# design.net
KiCad netlist of a schematic drawn in Altium Designer
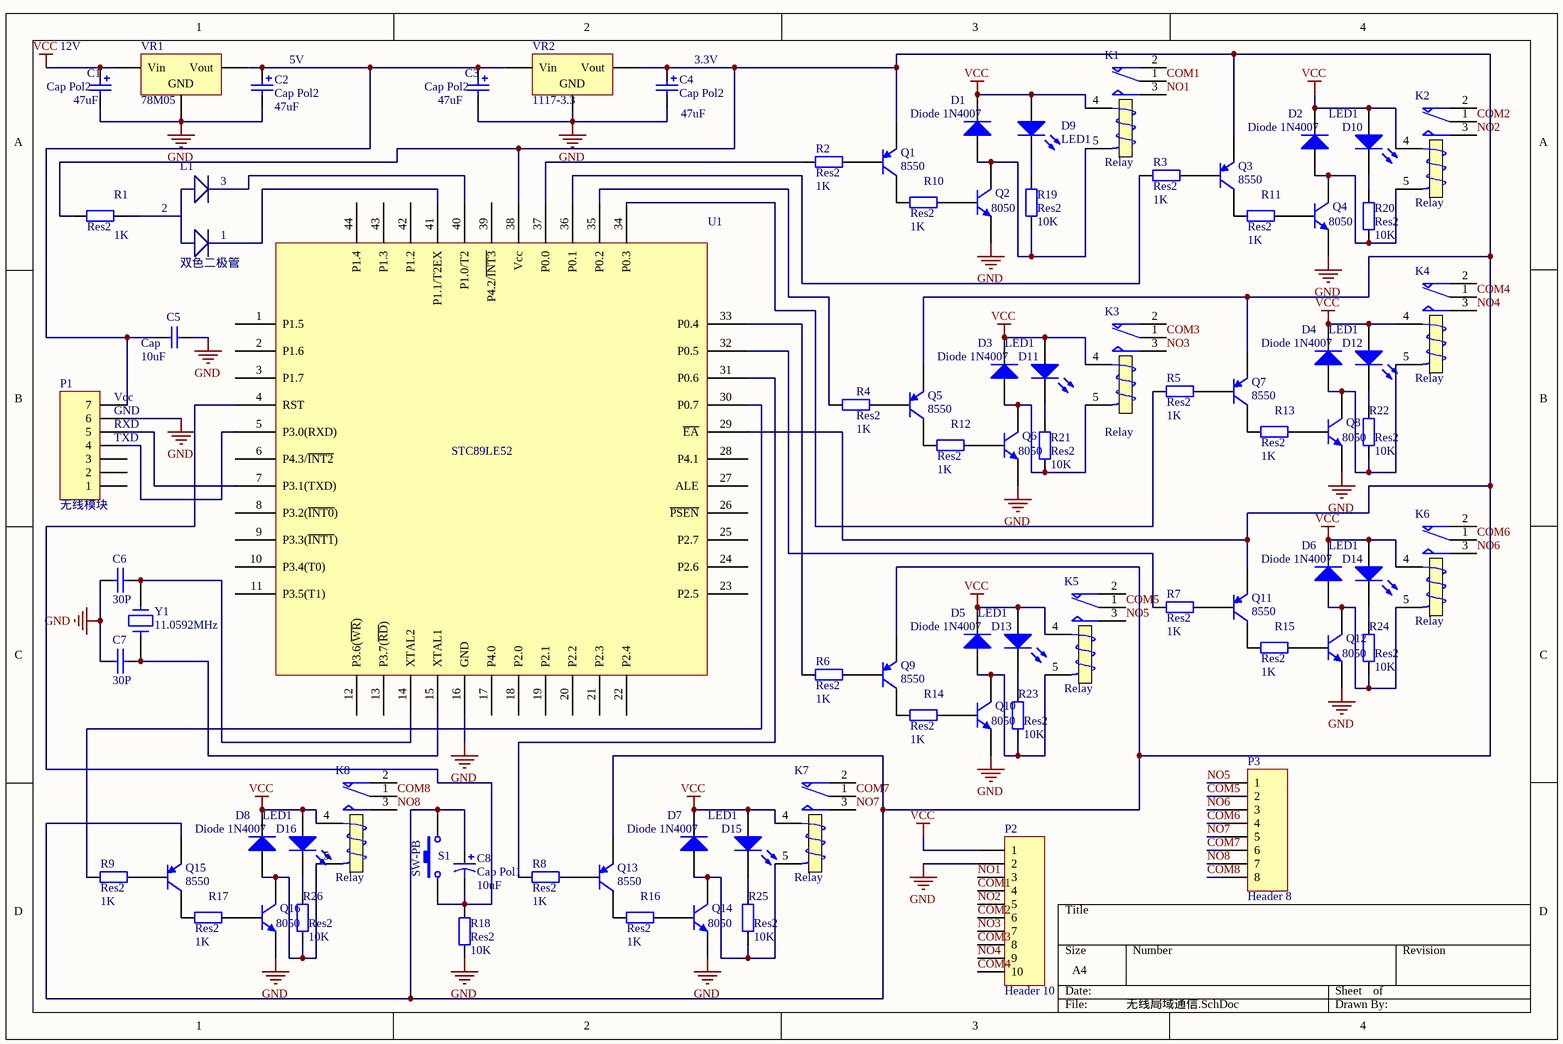
[diagram p0: 无线局域通信.SchDoc]

(export (version "E")
  (design (tool "Eeschema 10.0.6"))
  (components
    (comp (ref "C1")
      (value "Cap Pol2")
      (footprint "CAP_D6_3MM")
      (description "Polarized Capacitor (Axial)")
      (fields (field (name "ALTIUM_VALUE") "47uF") (field (name "PUBLISHER") "Altium Limited"))
      (libsource (lib "Miscellaneous Devices") (part "Cap Pol2"))
    )
    (comp (ref "C2")
      (value "Cap Pol2")
      (footprint "CAP_D6_3MM")
      (description "Polarized Capacitor (Axial)")
      (fields (field (name "ALTIUM_VALUE") "47uF") (field (name "PUBLISHER") "Altium Limited"))
      (libsource (lib "Miscellaneous Devices") (part "Cap Pol2"))
    )
    (comp (ref "C3")
      (value "Cap Pol2")
      (footprint "CAP_D6_3MM")
      (description "Polarized Capacitor (Axial)")
      (fields (field (name "ALTIUM_VALUE") "47uF") (field (name "PUBLISHER") "Altium Limited"))
      (libsource (lib "Miscellaneous Devices") (part "Cap Pol2"))
    )
    (comp (ref "C4")
      (value "Cap Pol2")
      (footprint "CAP_D6_3MM")
      (description "Polarized Capacitor (Axial)")
      (fields (field (name "ALTIUM_VALUE") "47uF") (field (name "PUBLISHER") "Altium Limited"))
      (libsource (lib "Miscellaneous Devices") (part "Cap Pol2"))
    )
    (comp (ref "C5")
      (value "Cap")
      (footprint "RAD0.1")
      (description "Capacitor")
      (fields (field (name "ALTIUM_VALUE") "10uF") (field (name "PUBLISHER") "Altium Limited"))
      (libsource (lib "Miscellaneous Devices") (part "Cap"))
    )
    (comp (ref "C6")
      (value "30P")
      (footprint "0603")
      (description "Capacitor")
      (libsource (lib "*") (part "MY_C_CAP"))
    )
    (comp (ref "C7")
      (value "30P")
      (footprint "0603")
      (description "Capacitor")
      (libsource (lib "*") (part "MY_C_CAP"))
    )
    (comp (ref "C8")
      (value "Cap Pol1")
      (footprint "CAP_D6_3MM")
      (description "Polarized Capacitor (Radial)")
      (fields (field (name "ALTIUM_VALUE") "10uF") (field (name "PUBLISHER") "Altium Limited"))
      (libsource (lib "Miscellaneous Devices") (part "Cap Pol1"))
    )
    (comp (ref "D1")
      (value "Diode 1N4007")
      (footprint "DO-41")
      (description "1 Amp General Purpose Rectifier")
      (fields (field (name "PUBLISHER") "Altium Limited"))
      (libsource (lib "Miscellaneous Devices") (part "Diode 1N4007"))
    )
    (comp (ref "D2")
      (value "Diode 1N4007")
      (footprint "DO-41")
      (description "1 Amp General Purpose Rectifier")
      (fields (field (name "PUBLISHER") "Altium Limited"))
      (libsource (lib "Miscellaneous Devices") (part "Diode 1N4007"))
    )
    (comp (ref "D3")
      (value "Diode 1N4007")
      (footprint "DO-41")
      (description "1 Amp General Purpose Rectifier")
      (fields (field (name "PUBLISHER") "Altium Limited"))
      (libsource (lib "Miscellaneous Devices") (part "Diode 1N4007"))
    )
    (comp (ref "D4")
      (value "Diode 1N4007")
      (footprint "DO-41")
      (description "1 Amp General Purpose Rectifier")
      (fields (field (name "PUBLISHER") "Altium Limited"))
      (libsource (lib "Miscellaneous Devices") (part "Diode 1N4007"))
    )
    (comp (ref "D5")
      (value "Diode 1N4007")
      (footprint "DO-41")
      (description "1 Amp General Purpose Rectifier")
      (fields (field (name "PUBLISHER") "Altium Limited"))
      (libsource (lib "Miscellaneous Devices") (part "Diode 1N4007"))
    )
    (comp (ref "D6")
      (value "Diode 1N4007")
      (footprint "DO-41")
      (description "1 Amp General Purpose Rectifier")
      (fields (field (name "PUBLISHER") "Altium Limited"))
      (libsource (lib "Miscellaneous Devices") (part "Diode 1N4007"))
    )
    (comp (ref "D7")
      (value "Diode 1N4007")
      (footprint "DO-41")
      (description "1 Amp General Purpose Rectifier")
      (fields (field (name "PUBLISHER") "Altium Limited"))
      (libsource (lib "Miscellaneous Devices") (part "Diode 1N4007"))
    )
    (comp (ref "D8")
      (value "Diode 1N4007")
      (footprint "DO-41")
      (description "1 Amp General Purpose Rectifier")
      (fields (field (name "PUBLISHER") "Altium Limited"))
      (libsource (lib "Miscellaneous Devices") (part "Diode 1N4007"))
    )
    (comp (ref "D9")
      (value "LED1")
      (footprint "LED-1")
      (description "Typical RED GaAs LED")
      (fields (field (name "PUBLISHER") "Altium Limited"))
      (libsource (lib "Miscellaneous Devices") (part "LED1"))
    )
    (comp (ref "D10")
      (value "LED1")
      (footprint "LED-1")
      (description "Typical RED GaAs LED")
      (fields (field (name "PUBLISHER") "Altium Limited"))
      (libsource (lib "Miscellaneous Devices") (part "LED1"))
    )
    (comp (ref "D11")
      (value "LED1")
      (footprint "LED-1")
      (description "Typical RED GaAs LED")
      (fields (field (name "PUBLISHER") "Altium Limited"))
      (libsource (lib "Miscellaneous Devices") (part "LED1"))
    )
    (comp (ref "D12")
      (value "LED1")
      (footprint "LED-1")
      (description "Typical RED GaAs LED")
      (fields (field (name "PUBLISHER") "Altium Limited"))
      (libsource (lib "Miscellaneous Devices") (part "LED1"))
    )
    (comp (ref "D13")
      (value "LED1")
      (footprint "LED-1")
      (description "Typical RED GaAs LED")
      (fields (field (name "PUBLISHER") "Altium Limited"))
      (libsource (lib "Miscellaneous Devices") (part "LED1"))
    )
    (comp (ref "D14")
      (value "LED1")
      (footprint "LED-1")
      (description "Typical RED GaAs LED")
      (fields (field (name "PUBLISHER") "Altium Limited"))
      (libsource (lib "Miscellaneous Devices") (part "LED1"))
    )
    (comp (ref "D15")
      (value "LED1")
      (footprint "LED-1")
      (description "Typical RED GaAs LED")
      (fields (field (name "PUBLISHER") "Altium Limited"))
      (libsource (lib "Miscellaneous Devices") (part "LED1"))
    )
    (comp (ref "D16")
      (value "LED1")
      (footprint "LED-1")
      (description "Typical RED GaAs LED")
      (fields (field (name "PUBLISHER") "Altium Limited"))
      (libsource (lib "Miscellaneous Devices") (part "LED1"))
    )
    (comp (ref "K1")
      (value "Relay")
      (footprint "继电器")
      (description "SPDT Relay")
      (fields (field (name "PUBLISHER") "Altium Limited"))
      (libsource (lib "Miscellaneous Devices") (part "Relay"))
    )
    (comp (ref "K2")
      (value "Relay")
      (footprint "继电器")
      (description "SPDT Relay")
      (fields (field (name "PUBLISHER") "Altium Limited"))
      (libsource (lib "Miscellaneous Devices") (part "Relay"))
    )
    (comp (ref "K3")
      (value "Relay")
      (footprint "继电器")
      (description "SPDT Relay")
      (fields (field (name "PUBLISHER") "Altium Limited"))
      (libsource (lib "Miscellaneous Devices") (part "Relay"))
    )
    (comp (ref "K4")
      (value "Relay")
      (footprint "继电器")
      (description "SPDT Relay")
      (fields (field (name "PUBLISHER") "Altium Limited"))
      (libsource (lib "Miscellaneous Devices") (part "Relay"))
    )
    (comp (ref "K5")
      (value "Relay")
      (footprint "继电器")
      (description "SPDT Relay")
      (fields (field (name "PUBLISHER") "Altium Limited"))
      (libsource (lib "Miscellaneous Devices") (part "Relay"))
    )
    (comp (ref "K6")
      (value "Relay")
      (footprint "继电器")
      (description "SPDT Relay")
      (fields (field (name "PUBLISHER") "Altium Limited"))
      (libsource (lib "Miscellaneous Devices") (part "Relay"))
    )
    (comp (ref "K7")
      (value "Relay")
      (footprint "继电器")
      (description "SPDT Relay")
      (fields (field (name "PUBLISHER") "Altium Limited"))
      (libsource (lib "Miscellaneous Devices") (part "Relay"))
    )
    (comp (ref "K8")
      (value "Relay")
      (footprint "继电器")
      (description "SPDT Relay")
      (fields (field (name "PUBLISHER") "Altium Limited"))
      (libsource (lib "Miscellaneous Devices") (part "Relay"))
    )
    (comp (ref "L1") (value "双色二极管") (footprint "TO-205AF") (libsource (lib "PCB_Project1") (part "双色二极管")))
    (comp (ref "P1")
      (value "无线模块")
      (footprint "P1")
      (description "Header, 7-Pin")
      (fields (field (name "PUBLISHER") "Altium Limited"))
      (libsource (lib "Miscellaneous Connectors") (part "MHDR1X7"))
    )
    (comp (ref "P2")
      (value "Header 10")
      (footprint "P2")
      (description "Header, 10-Pin")
      (fields (field (name "PUBLISHER") "Altium Limited"))
      (libsource (lib "Miscellaneous Connectors") (part "Header 10"))
    )
    (comp (ref "P3")
      (value "Header 8")
      (footprint "P3")
      (description "Header, 8-Pin")
      (fields (field (name "PUBLISHER") "Altium Limited"))
      (libsource (lib "Miscellaneous Connectors") (part "Header 8"))
    )
    (comp (ref "Q1")
      (value "8550")
      (footprint "SOT-23B_N")
      (description "PNP Bipolar Transistor")
      (fields (field (name "PUBLISHER") "Altium Limited"))
      (libsource (lib "Miscellaneous Devices") (part "PNP"))
    )
    (comp (ref "Q2")
      (value "8050")
      (footprint "SOT-23B_N")
      (description "NPN Bipolar Transistor")
      (fields (field (name "PUBLISHER") "Altium Limited"))
      (libsource (lib "Miscellaneous Devices") (part "QNPN"))
    )
    (comp (ref "Q3")
      (value "8550")
      (footprint "SOT-23B_N")
      (description "PNP Bipolar Transistor")
      (fields (field (name "PUBLISHER") "Altium Limited"))
      (libsource (lib "Miscellaneous Devices") (part "PNP"))
    )
    (comp (ref "Q4")
      (value "8050")
      (footprint "SOT-23B_N")
      (description "NPN Bipolar Transistor")
      (fields (field (name "PUBLISHER") "Altium Limited"))
      (libsource (lib "Miscellaneous Devices") (part "QNPN"))
    )
    (comp (ref "Q5")
      (value "8550")
      (footprint "SOT-23B_N")
      (description "PNP Bipolar Transistor")
      (fields (field (name "PUBLISHER") "Altium Limited"))
      (libsource (lib "Miscellaneous Devices") (part "PNP"))
    )
    (comp (ref "Q6")
      (value "8050")
      (footprint "SOT-23B_N")
      (description "NPN Bipolar Transistor")
      (fields (field (name "PUBLISHER") "Altium Limited"))
      (libsource (lib "Miscellaneous Devices") (part "QNPN"))
    )
    (comp (ref "Q7")
      (value "8550")
      (footprint "SOT-23B_N")
      (description "PNP Bipolar Transistor")
      (fields (field (name "PUBLISHER") "Altium Limited"))
      (libsource (lib "Miscellaneous Devices") (part "PNP"))
    )
    (comp (ref "Q8")
      (value "8050")
      (footprint "SOT-23B_N")
      (description "NPN Bipolar Transistor")
      (fields (field (name "PUBLISHER") "Altium Limited"))
      (libsource (lib "Miscellaneous Devices") (part "QNPN"))
    )
    (comp (ref "Q9")
      (value "8550")
      (footprint "SOT-23B_N")
      (description "PNP Bipolar Transistor")
      (fields (field (name "PUBLISHER") "Altium Limited"))
      (libsource (lib "Miscellaneous Devices") (part "PNP"))
    )
    (comp (ref "Q10")
      (value "8050")
      (footprint "SOT-23B_N")
      (description "NPN Bipolar Transistor")
      (fields (field (name "PUBLISHER") "Altium Limited"))
      (libsource (lib "Miscellaneous Devices") (part "QNPN"))
    )
    (comp (ref "Q11")
      (value "8550")
      (footprint "SOT-23B_N")
      (description "PNP Bipolar Transistor")
      (fields (field (name "PUBLISHER") "Altium Limited"))
      (libsource (lib "Miscellaneous Devices") (part "PNP"))
    )
    (comp (ref "Q12")
      (value "8050")
      (footprint "SOT-23B_N")
      (description "NPN Bipolar Transistor")
      (fields (field (name "PUBLISHER") "Altium Limited"))
      (libsource (lib "Miscellaneous Devices") (part "QNPN"))
    )
    (comp (ref "Q13")
      (value "8550")
      (footprint "SOT-23B_N")
      (description "PNP Bipolar Transistor")
      (fields (field (name "PUBLISHER") "Altium Limited"))
      (libsource (lib "Miscellaneous Devices") (part "PNP"))
    )
    (comp (ref "Q14")
      (value "8050")
      (footprint "SOT-23B_N")
      (description "NPN Bipolar Transistor")
      (fields (field (name "PUBLISHER") "Altium Limited"))
      (libsource (lib "Miscellaneous Devices") (part "QNPN"))
    )
    (comp (ref "Q15")
      (value "8550")
      (footprint "SOT-23B_N")
      (description "PNP Bipolar Transistor")
      (fields (field (name "PUBLISHER") "Altium Limited"))
      (libsource (lib "Miscellaneous Devices") (part "PNP"))
    )
    (comp (ref "Q16")
      (value "8050")
      (footprint "SOT-23B_N")
      (description "NPN Bipolar Transistor")
      (fields (field (name "PUBLISHER") "Altium Limited"))
      (libsource (lib "Miscellaneous Devices") (part "QNPN"))
    )
    (comp (ref "R1")
      (value "Res2")
      (footprint "0603")
      (description "Resistor")
      (fields (field (name "ALTIUM_VALUE") "1K") (field (name "PUBLISHER") "Altium Limited"))
      (libsource (lib "") (part "Res2_1"))
    )
    (comp (ref "R2")
      (value "Res2")
      (footprint "0603")
      (description "Resistor")
      (fields (field (name "ALTIUM_VALUE") "1K") (field (name "PUBLISHER") "Altium Limited"))
      (libsource (lib "") (part "Res2_1"))
    )
    (comp (ref "R3")
      (value "Res2")
      (footprint "0603")
      (description "Resistor")
      (fields (field (name "ALTIUM_VALUE") "1K") (field (name "PUBLISHER") "Altium Limited"))
      (libsource (lib "") (part "Res2_1"))
    )
    (comp (ref "R4")
      (value "Res2")
      (footprint "0603")
      (description "Resistor")
      (fields (field (name "ALTIUM_VALUE") "1K") (field (name "PUBLISHER") "Altium Limited"))
      (libsource (lib "") (part "Res2_1"))
    )
    (comp (ref "R5")
      (value "Res2")
      (footprint "0603")
      (description "Resistor")
      (fields (field (name "ALTIUM_VALUE") "1K") (field (name "PUBLISHER") "Altium Limited"))
      (libsource (lib "") (part "Res2_1"))
    )
    (comp (ref "R6")
      (value "Res2")
      (footprint "0603")
      (description "Resistor")
      (fields (field (name "ALTIUM_VALUE") "1K") (field (name "PUBLISHER") "Altium Limited"))
      (libsource (lib "") (part "Res2_1"))
    )
    (comp (ref "R7")
      (value "Res2")
      (footprint "0603")
      (description "Resistor")
      (fields (field (name "ALTIUM_VALUE") "1K") (field (name "PUBLISHER") "Altium Limited"))
      (libsource (lib "") (part "Res2_1"))
    )
    (comp (ref "R8")
      (value "Res2")
      (footprint "0603")
      (description "Resistor")
      (fields (field (name "ALTIUM_VALUE") "1K") (field (name "PUBLISHER") "Altium Limited"))
      (libsource (lib "") (part "Res2_1"))
    )
    (comp (ref "R9")
      (value "Res2")
      (footprint "0603")
      (description "Resistor")
      (fields (field (name "ALTIUM_VALUE") "1K") (field (name "PUBLISHER") "Altium Limited"))
      (libsource (lib "") (part "Res2_1"))
    )
    (comp (ref "R10")
      (value "Res2")
      (footprint "0603")
      (description "Resistor")
      (fields (field (name "ALTIUM_VALUE") "1K") (field (name "PUBLISHER") "Altium Limited"))
      (libsource (lib "") (part "Res2_1"))
    )
    (comp (ref "R11")
      (value "Res2")
      (footprint "0603")
      (description "Resistor")
      (fields (field (name "ALTIUM_VALUE") "1K") (field (name "PUBLISHER") "Altium Limited"))
      (libsource (lib "") (part "Res2_1"))
    )
    (comp (ref "R12")
      (value "Res2")
      (footprint "0603")
      (description "Resistor")
      (fields (field (name "ALTIUM_VALUE") "1K") (field (name "PUBLISHER") "Altium Limited"))
      (libsource (lib "") (part "Res2_1"))
    )
    (comp (ref "R13")
      (value "Res2")
      (footprint "0603")
      (description "Resistor")
      (fields (field (name "ALTIUM_VALUE") "1K") (field (name "PUBLISHER") "Altium Limited"))
      (libsource (lib "") (part "Res2_1"))
    )
    (comp (ref "R14")
      (value "Res2")
      (footprint "0603")
      (description "Resistor")
      (fields (field (name "ALTIUM_VALUE") "1K") (field (name "PUBLISHER") "Altium Limited"))
      (libsource (lib "") (part "Res2_1"))
    )
    (comp (ref "R15")
      (value "Res2")
      (footprint "0603")
      (description "Resistor")
      (fields (field (name "ALTIUM_VALUE") "1K") (field (name "PUBLISHER") "Altium Limited"))
      (libsource (lib "") (part "Res2_1"))
    )
    (comp (ref "R16")
      (value "Res2")
      (footprint "0603")
      (description "Resistor")
      (fields (field (name "ALTIUM_VALUE") "1K") (field (name "PUBLISHER") "Altium Limited"))
      (libsource (lib "") (part "Res2_1"))
    )
    (comp (ref "R17")
      (value "Res2")
      (footprint "0603")
      (description "Resistor")
      (fields (field (name "ALTIUM_VALUE") "1K") (field (name "PUBLISHER") "Altium Limited"))
      (libsource (lib "") (part "Res2_1"))
    )
    (comp (ref "R18")
      (value "Res2")
      (footprint "0603")
      (description "Resistor")
      (fields (field (name "ALTIUM_VALUE") "10K") (field (name "PUBLISHER") "Altium Limited"))
      (libsource (lib "Miscellaneous Devices") (part "Res2"))
    )
    (comp (ref "R19")
      (value "Res2")
      (footprint "0603")
      (description "Resistor")
      (fields (field (name "ALTIUM_VALUE") "10K") (field (name "PUBLISHER") "Altium Limited"))
      (libsource (lib "Miscellaneous Devices") (part "Res2"))
    )
    (comp (ref "R20")
      (value "Res2")
      (footprint "0603")
      (description "Resistor")
      (fields (field (name "ALTIUM_VALUE") "10K") (field (name "PUBLISHER") "Altium Limited"))
      (libsource (lib "Miscellaneous Devices") (part "Res2"))
    )
    (comp (ref "R21")
      (value "Res2")
      (footprint "0603")
      (description "Resistor")
      (fields (field (name "ALTIUM_VALUE") "10K") (field (name "PUBLISHER") "Altium Limited"))
      (libsource (lib "Miscellaneous Devices") (part "Res2"))
    )
    (comp (ref "R22")
      (value "Res2")
      (footprint "0603")
      (description "Resistor")
      (fields (field (name "ALTIUM_VALUE") "10K") (field (name "PUBLISHER") "Altium Limited"))
      (libsource (lib "Miscellaneous Devices") (part "Res2"))
    )
    (comp (ref "R23")
      (value "Res2")
      (footprint "0603")
      (description "Resistor")
      (fields (field (name "ALTIUM_VALUE") "10K") (field (name "PUBLISHER") "Altium Limited"))
      (libsource (lib "Miscellaneous Devices") (part "Res2"))
    )
    (comp (ref "R24")
      (value "Res2")
      (footprint "0603")
      (description "Resistor")
      (fields (field (name "ALTIUM_VALUE") "10K") (field (name "PUBLISHER") "Altium Limited"))
      (libsource (lib "Miscellaneous Devices") (part "Res2"))
    )
    (comp (ref "R25")
      (value "Res2")
      (footprint "0603")
      (description "Resistor")
      (fields (field (name "ALTIUM_VALUE") "10K") (field (name "PUBLISHER") "Altium Limited"))
      (libsource (lib "Miscellaneous Devices") (part "Res2"))
    )
    (comp (ref "R26")
      (value "Res2")
      (footprint "0603")
      (description "Resistor")
      (fields (field (name "ALTIUM_VALUE") "10K") (field (name "PUBLISHER") "Altium Limited"))
      (libsource (lib "Miscellaneous Devices") (part "Res2"))
    )
    (comp (ref "S1")
      (value "SW-PB")
      (footprint "轻触开关")
      (description "Switch")
      (fields (field (name "PUBLISHER") "Altium Limited"))
      (libsource (lib "Miscellaneous Devices") (part "SW-PB"))
    )
    (comp (ref "U1")
      (value "STC89LE52")
      (footprint "LQFP44_10X10X08P")
      (libsource (lib "无线局域通信") (part "STC89LE52"))
    )
    (comp (ref "VR1")
      (value "78M05")
      (footprint "TO-252-2L")
      (description "Voltage Regulator")
      (fields (field (name "PUBLISHER") "Altium Limited"))
      (libsource (lib "Miscellaneous Devices") (part "Volt Reg"))
    )
    (comp (ref "VR2")
      (value "1117-3.3")
      (footprint "SOT-223")
      (description "Voltage Regulator")
      (fields (field (name "PUBLISHER") "Altium Limited"))
      (libsource (lib "") (part "Volt Reg_1"))
    )
    (comp (ref "Y1")
      (value "11.0592MHz")
      (footprint "49S")
      (description "Crystal")
      (libsource (lib "*") (part "CRYSTAL"))
    )
  )
  (nets
    (net (code "1") (name "/COM1") (class "Default")
      (node (ref "K1") (pin "1") (pinfunction "COM_1") (pintype "passive"))
      (node (ref "P2") (pin "4") (pinfunction "4_4") (pintype "passive"))
    )
    (net (code "2") (name "/COM2") (class "Default")
      (node (ref "K2") (pin "1") (pinfunction "COM_1") (pintype "passive"))
      (node (ref "P2") (pin "6") (pinfunction "6_6") (pintype "passive"))
    )
    (net (code "3") (name "/COM3") (class "Default")
      (node (ref "K3") (pin "1") (pinfunction "COM_1") (pintype "passive"))
      (node (ref "P2") (pin "8") (pinfunction "8_8") (pintype "passive"))
    )
    (net (code "4") (name "/COM4") (class "Default")
      (node (ref "K4") (pin "1") (pinfunction "COM_1") (pintype "passive"))
      (node (ref "P2") (pin "10") (pinfunction "10_10") (pintype "passive"))
    )
    (net (code "5") (name "/COM5") (class "Default")
      (node (ref "K5") (pin "1") (pinfunction "COM_1") (pintype "passive"))
      (node (ref "P3") (pin "2") (pinfunction "2_2") (pintype "passive"))
    )
    (net (code "6") (name "/COM6") (class "Default")
      (node (ref "K6") (pin "1") (pinfunction "COM_1") (pintype "passive"))
      (node (ref "P3") (pin "4") (pinfunction "4_4") (pintype "passive"))
    )
    (net (code "7") (name "/COM7") (class "Default")
      (node (ref "K7") (pin "1") (pinfunction "COM_1") (pintype "passive"))
      (node (ref "P3") (pin "6") (pinfunction "6_6") (pintype "passive"))
    )
    (net (code "8") (name "/COM8") (class "Default")
      (node (ref "K8") (pin "1") (pinfunction "COM_1") (pintype "passive"))
      (node (ref "P3") (pin "8") (pinfunction "8_8") (pintype "passive"))
    )
    (net (code "9") (name "/NO1") (class "Default")
      (node (ref "K1") (pin "3") (pinfunction "NO_3") (pintype "passive"))
      (node (ref "P2") (pin "3") (pinfunction "3_3") (pintype "passive"))
    )
    (net (code "10") (name "/NO2") (class "Default")
      (node (ref "K2") (pin "3") (pinfunction "NO_3") (pintype "passive"))
      (node (ref "P2") (pin "5") (pinfunction "5_5") (pintype "passive"))
    )
    (net (code "11") (name "/NO3") (class "Default")
      (node (ref "K3") (pin "3") (pinfunction "NO_3") (pintype "passive"))
      (node (ref "P2") (pin "7") (pinfunction "7_7") (pintype "passive"))
    )
    (net (code "12") (name "/NO4") (class "Default")
      (node (ref "K4") (pin "3") (pinfunction "NO_3") (pintype "passive"))
      (node (ref "P2") (pin "9") (pinfunction "9_9") (pintype "passive"))
    )
    (net (code "13") (name "/NO5") (class "Default")
      (node (ref "K5") (pin "3") (pinfunction "NO_3") (pintype "passive"))
      (node (ref "P3") (pin "1") (pinfunction "1_1") (pintype "passive"))
    )
    (net (code "14") (name "/NO6") (class "Default")
      (node (ref "K6") (pin "3") (pinfunction "NO_3") (pintype "passive"))
      (node (ref "P3") (pin "3") (pinfunction "3_3") (pintype "passive"))
    )
    (net (code "15") (name "/NO7") (class "Default")
      (node (ref "K7") (pin "3") (pinfunction "NO_3") (pintype "passive"))
      (node (ref "P3") (pin "5") (pinfunction "5_5") (pintype "passive"))
    )
    (net (code "16") (name "/NO8") (class "Default")
      (node (ref "K8") (pin "3") (pinfunction "NO_3") (pintype "passive"))
      (node (ref "P3") (pin "7") (pinfunction "7_7") (pintype "passive"))
    )
    (net (code "17") (name "GND") (class "Default")
      (node (ref "C1") (pin "2") (pinfunction "2_2") (pintype "passive"))
      (node (ref "C2") (pin "2") (pinfunction "2_2") (pintype "passive"))
      (node (ref "C3") (pin "2") (pinfunction "2_2") (pintype "passive"))
      (node (ref "C4") (pin "2") (pinfunction "2_2") (pintype "passive"))
      (node (ref "C5") (pin "2") (pinfunction "2_2") (pintype "passive"))
      (node (ref "C6") (pin "1") (pinfunction "1_1") (pintype "passive"))
      (node (ref "C7") (pin "1") (pinfunction "1_1") (pintype "passive"))
      (node (ref "P1") (pin "6") (pinfunction "6_6") (pintype "passive"))
      (node (ref "P2") (pin "2") (pinfunction "2_2") (pintype "passive"))
      (node (ref "Q10") (pin "2") (pinfunction "E_2") (pintype "passive"))
      (node (ref "Q12") (pin "2") (pinfunction "E_2") (pintype "passive"))
      (node (ref "Q14") (pin "2") (pinfunction "E_2") (pintype "passive"))
      (node (ref "Q16") (pin "2") (pinfunction "E_2") (pintype "passive"))
      (node (ref "Q2") (pin "2") (pinfunction "E_2") (pintype "passive"))
      (node (ref "Q4") (pin "2") (pinfunction "E_2") (pintype "passive"))
      (node (ref "Q6") (pin "2") (pinfunction "E_2") (pintype "passive"))
      (node (ref "Q8") (pin "2") (pinfunction "E_2") (pintype "passive"))
      (node (ref "R18") (pin "1") (pinfunction "1_1") (pintype "passive"))
      (node (ref "U1") (pin "16") (pinfunction "GND_16") (pintype "passive"))
      (node (ref "VR1") (pin "2") (pinfunction "GND_2") (pintype "passive"))
      (node (ref "VR2") (pin "1") (pinfunction "GND_1") (pintype "passive"))
    )
    (net (code "18") (name "Net-(D1-A)") (class "Default")
      (node (ref "D1") (pin "2") (pinfunction "A_2") (pintype "passive"))
      (node (ref "K1") (pin "5") (pinfunction "T2_5") (pintype "passive"))
      (node (ref "Q2") (pin "3") (pinfunction "C_3") (pintype "passive"))
      (node (ref "R19") (pin "1") (pinfunction "1_1") (pintype "passive"))
    )
    (net (code "19") (name "Net-(D2-A)") (class "Default")
      (node (ref "D2") (pin "2") (pinfunction "A_2") (pintype "passive"))
      (node (ref "K2") (pin "5") (pinfunction "T2_5") (pintype "passive"))
      (node (ref "Q4") (pin "3") (pinfunction "C_3") (pintype "passive"))
      (node (ref "R20") (pin "1") (pinfunction "1_1") (pintype "passive"))
    )
    (net (code "20") (name "Net-(D3-A)") (class "Default")
      (node (ref "D3") (pin "2") (pinfunction "A_2") (pintype "passive"))
      (node (ref "K3") (pin "5") (pinfunction "T2_5") (pintype "passive"))
      (node (ref "Q6") (pin "3") (pinfunction "C_3") (pintype "passive"))
      (node (ref "R21") (pin "1") (pinfunction "1_1") (pintype "passive"))
    )
    (net (code "21") (name "Net-(D4-A)") (class "Default")
      (node (ref "D4") (pin "2") (pinfunction "A_2") (pintype "passive"))
      (node (ref "K4") (pin "5") (pinfunction "T2_5") (pintype "passive"))
      (node (ref "Q8") (pin "3") (pinfunction "C_3") (pintype "passive"))
      (node (ref "R22") (pin "1") (pinfunction "1_1") (pintype "passive"))
    )
    (net (code "22") (name "Net-(D5-A)") (class "Default")
      (node (ref "D5") (pin "2") (pinfunction "A_2") (pintype "passive"))
      (node (ref "K5") (pin "5") (pinfunction "T2_5") (pintype "passive"))
      (node (ref "Q10") (pin "3") (pinfunction "C_3") (pintype "passive"))
      (node (ref "R23") (pin "1") (pinfunction "1_1") (pintype "passive"))
    )
    (net (code "23") (name "Net-(D6-A)") (class "Default")
      (node (ref "D6") (pin "2") (pinfunction "A_2") (pintype "passive"))
      (node (ref "K6") (pin "5") (pinfunction "T2_5") (pintype "passive"))
      (node (ref "Q12") (pin "3") (pinfunction "C_3") (pintype "passive"))
      (node (ref "R24") (pin "1") (pinfunction "1_1") (pintype "passive"))
    )
    (net (code "24") (name "Net-(D7-A)") (class "Default")
      (node (ref "D7") (pin "2") (pinfunction "A_2") (pintype "passive"))
      (node (ref "K7") (pin "5") (pinfunction "T2_5") (pintype "passive"))
      (node (ref "Q14") (pin "3") (pinfunction "C_3") (pintype "passive"))
      (node (ref "R25") (pin "1") (pinfunction "1_1") (pintype "passive"))
    )
    (net (code "25") (name "Net-(D8-A)") (class "Default")
      (node (ref "D8") (pin "2") (pinfunction "A_2") (pintype "passive"))
      (node (ref "K8") (pin "5") (pinfunction "T2_5") (pintype "passive"))
      (node (ref "Q16") (pin "3") (pinfunction "C_3") (pintype "passive"))
      (node (ref "R26") (pin "1") (pinfunction "1_1") (pintype "passive"))
    )
    (net (code "26") (name "Net-(D9-K)") (class "Default")
      (node (ref "D9") (pin "2") (pinfunction "K_2") (pintype "passive"))
      (node (ref "R19") (pin "2") (pinfunction "2_2") (pintype "passive"))
    )
    (net (code "27") (name "Net-(D10-K)") (class "Default")
      (node (ref "D10") (pin "2") (pinfunction "K_2") (pintype "passive"))
      (node (ref "R20") (pin "2") (pinfunction "2_2") (pintype "passive"))
    )
    (net (code "28") (name "Net-(D11-K)") (class "Default")
      (node (ref "D11") (pin "2") (pinfunction "K_2") (pintype "passive"))
      (node (ref "R21") (pin "2") (pinfunction "2_2") (pintype "passive"))
    )
    (net (code "29") (name "Net-(D12-K)") (class "Default")
      (node (ref "D12") (pin "2") (pinfunction "K_2") (pintype "passive"))
      (node (ref "R22") (pin "2") (pinfunction "2_2") (pintype "passive"))
    )
    (net (code "30") (name "Net-(D13-K)") (class "Default")
      (node (ref "D13") (pin "2") (pinfunction "K_2") (pintype "passive"))
      (node (ref "R23") (pin "2") (pinfunction "2_2") (pintype "passive"))
    )
    (net (code "31") (name "Net-(D14-K)") (class "Default")
      (node (ref "D14") (pin "2") (pinfunction "K_2") (pintype "passive"))
      (node (ref "R24") (pin "2") (pinfunction "2_2") (pintype "passive"))
    )
    (net (code "32") (name "Net-(D15-K)") (class "Default")
      (node (ref "D15") (pin "2") (pinfunction "K_2") (pintype "passive"))
      (node (ref "R25") (pin "2") (pinfunction "2_2") (pintype "passive"))
    )
    (net (code "33") (name "Net-(D16-K)") (class "Default")
      (node (ref "D16") (pin "2") (pinfunction "K_2") (pintype "passive"))
      (node (ref "R26") (pin "2") (pinfunction "2_2") (pintype "passive"))
    )
    (net (code "34") (name "Net-(L1-Pad2)") (class "Default")
      (node (ref "L1") (pin "2") (pinfunction "2_2") (pintype "passive"))
      (node (ref "R1") (pin "2") (pinfunction "2_2") (pintype "passive"))
    )
    (net (code "35") (name "Net-(Q1-B)") (class "Default")
      (node (ref "Q1") (pin "1") (pinfunction "B_1") (pintype "passive"))
      (node (ref "R2") (pin "2") (pinfunction "2_2") (pintype "passive"))
    )
    (net (code "36") (name "Net-(Q1-C)") (class "Default")
      (node (ref "Q1") (pin "3") (pinfunction "C_3") (pintype "passive"))
      (node (ref "R10") (pin "1") (pinfunction "1_1") (pintype "passive"))
    )
    (net (code "37") (name "Net-(Q1-E)") (class "Default")
      (node (ref "C4") (pin "1") (pinfunction "1_1") (pintype "passive"))
      (node (ref "C8") (pin "1") (pinfunction "1_1") (pintype "passive"))
      (node (ref "Q1") (pin "2") (pinfunction "E_2") (pintype "passive"))
      (node (ref "Q11") (pin "2") (pinfunction "E_2") (pintype "passive"))
      (node (ref "Q13") (pin "2") (pinfunction "E_2") (pintype "passive"))
      (node (ref "Q15") (pin "2") (pinfunction "E_2") (pintype "passive"))
      (node (ref "Q3") (pin "2") (pinfunction "E_2") (pintype "passive"))
      (node (ref "Q5") (pin "2") (pinfunction "E_2") (pintype "passive"))
      (node (ref "Q7") (pin "2") (pinfunction "E_2") (pintype "passive"))
      (node (ref "Q9") (pin "2") (pinfunction "E_2") (pintype "passive"))
      (node (ref "R1") (pin "1") (pinfunction "1_1") (pintype "passive"))
      (node (ref "S1") (pin "2") (pinfunction "2_2") (pintype "passive"))
      (node (ref "U1") (pin "29") (pinfunction "~{EA}_29") (pintype "passive"))
      (node (ref "U1") (pin "38") (pinfunction "Vcc_38") (pintype "passive"))
      (node (ref "VR2") (pin "2") (pinfunction "Vout_2") (pintype "passive"))
    )
    (net (code "38") (name "Net-(Q2-B)") (class "Default")
      (node (ref "Q2") (pin "1") (pinfunction "B_1") (pintype "passive"))
      (node (ref "R10") (pin "2") (pinfunction "2_2") (pintype "passive"))
    )
    (net (code "39") (name "Net-(Q3-B)") (class "Default")
      (node (ref "Q3") (pin "1") (pinfunction "B_1") (pintype "passive"))
      (node (ref "R3") (pin "2") (pinfunction "2_2") (pintype "passive"))
    )
    (net (code "40") (name "Net-(Q3-C)") (class "Default")
      (node (ref "Q3") (pin "3") (pinfunction "C_3") (pintype "passive"))
      (node (ref "R11") (pin "1") (pinfunction "1_1") (pintype "passive"))
    )
    (net (code "41") (name "Net-(Q4-B)") (class "Default")
      (node (ref "Q4") (pin "1") (pinfunction "B_1") (pintype "passive"))
      (node (ref "R11") (pin "2") (pinfunction "2_2") (pintype "passive"))
    )
    (net (code "42") (name "Net-(Q5-B)") (class "Default")
      (node (ref "Q5") (pin "1") (pinfunction "B_1") (pintype "passive"))
      (node (ref "R4") (pin "2") (pinfunction "2_2") (pintype "passive"))
    )
    (net (code "43") (name "Net-(Q5-C)") (class "Default")
      (node (ref "Q5") (pin "3") (pinfunction "C_3") (pintype "passive"))
      (node (ref "R12") (pin "1") (pinfunction "1_1") (pintype "passive"))
    )
    (net (code "44") (name "Net-(Q6-B)") (class "Default")
      (node (ref "Q6") (pin "1") (pinfunction "B_1") (pintype "passive"))
      (node (ref "R12") (pin "2") (pinfunction "2_2") (pintype "passive"))
    )
    (net (code "45") (name "Net-(Q7-B)") (class "Default")
      (node (ref "Q7") (pin "1") (pinfunction "B_1") (pintype "passive"))
      (node (ref "R5") (pin "2") (pinfunction "2_2") (pintype "passive"))
    )
    (net (code "46") (name "Net-(Q7-C)") (class "Default")
      (node (ref "Q7") (pin "3") (pinfunction "C_3") (pintype "passive"))
      (node (ref "R13") (pin "1") (pinfunction "1_1") (pintype "passive"))
    )
    (net (code "47") (name "Net-(Q8-B)") (class "Default")
      (node (ref "Q8") (pin "1") (pinfunction "B_1") (pintype "passive"))
      (node (ref "R13") (pin "2") (pinfunction "2_2") (pintype "passive"))
    )
    (net (code "48") (name "Net-(Q9-B)") (class "Default")
      (node (ref "Q9") (pin "1") (pinfunction "B_1") (pintype "passive"))
      (node (ref "R6") (pin "2") (pinfunction "2_2") (pintype "passive"))
    )
    (net (code "49") (name "Net-(Q9-C)") (class "Default")
      (node (ref "Q9") (pin "3") (pinfunction "C_3") (pintype "passive"))
      (node (ref "R14") (pin "1") (pinfunction "1_1") (pintype "passive"))
    )
    (net (code "50") (name "Net-(Q10-B)") (class "Default")
      (node (ref "Q10") (pin "1") (pinfunction "B_1") (pintype "passive"))
      (node (ref "R14") (pin "2") (pinfunction "2_2") (pintype "passive"))
    )
    (net (code "51") (name "Net-(Q11-B)") (class "Default")
      (node (ref "Q11") (pin "1") (pinfunction "B_1") (pintype "passive"))
      (node (ref "R7") (pin "2") (pinfunction "2_2") (pintype "passive"))
    )
    (net (code "52") (name "Net-(Q11-C)") (class "Default")
      (node (ref "Q11") (pin "3") (pinfunction "C_3") (pintype "passive"))
      (node (ref "R15") (pin "1") (pinfunction "1_1") (pintype "passive"))
    )
    (net (code "53") (name "Net-(Q12-B)") (class "Default")
      (node (ref "Q12") (pin "1") (pinfunction "B_1") (pintype "passive"))
      (node (ref "R15") (pin "2") (pinfunction "2_2") (pintype "passive"))
    )
    (net (code "54") (name "Net-(Q13-B)") (class "Default")
      (node (ref "Q13") (pin "1") (pinfunction "B_1") (pintype "passive"))
      (node (ref "R8") (pin "2") (pinfunction "2_2") (pintype "passive"))
    )
    (net (code "55") (name "Net-(Q13-C)") (class "Default")
      (node (ref "Q13") (pin "3") (pinfunction "C_3") (pintype "passive"))
      (node (ref "R16") (pin "1") (pinfunction "1_1") (pintype "passive"))
    )
    (net (code "56") (name "Net-(Q14-B)") (class "Default")
      (node (ref "Q14") (pin "1") (pinfunction "B_1") (pintype "passive"))
      (node (ref "R16") (pin "2") (pinfunction "2_2") (pintype "passive"))
    )
    (net (code "57") (name "Net-(Q15-B)") (class "Default")
      (node (ref "Q15") (pin "1") (pinfunction "B_1") (pintype "passive"))
      (node (ref "R9") (pin "2") (pinfunction "2_2") (pintype "passive"))
    )
    (net (code "58") (name "Net-(Q15-C)") (class "Default")
      (node (ref "Q15") (pin "3") (pinfunction "C_3") (pintype "passive"))
      (node (ref "R17") (pin "1") (pinfunction "1_1") (pintype "passive"))
    )
    (net (code "59") (name "Net-(Q16-B)") (class "Default")
      (node (ref "Q16") (pin "1") (pinfunction "B_1") (pintype "passive"))
      (node (ref "R17") (pin "2") (pinfunction "2_2") (pintype "passive"))
    )
    (net (code "60") (name "Net-(U1-P0.0)") (class "Default")
      (node (ref "R2") (pin "1") (pinfunction "1_1") (pintype "passive"))
      (node (ref "U1") (pin "37") (pinfunction "P0.0_37") (pintype "passive"))
    )
    (net (code "61") (name "Net-(U1-P0.1)") (class "Default")
      (node (ref "R3") (pin "1") (pinfunction "1_1") (pintype "passive"))
      (node (ref "U1") (pin "36") (pinfunction "P0.1_36") (pintype "passive"))
    )
    (net (code "62") (name "Net-(U1-P0.2)") (class "Default")
      (node (ref "R4") (pin "1") (pinfunction "1_1") (pintype "passive"))
      (node (ref "U1") (pin "35") (pinfunction "P0.2_35") (pintype "passive"))
    )
    (net (code "63") (name "Net-(U1-P0.3)") (class "Default")
      (node (ref "R5") (pin "1") (pinfunction "1_1") (pintype "passive"))
      (node (ref "U1") (pin "34") (pinfunction "P0.3_34") (pintype "passive"))
    )
    (net (code "64") (name "Net-(U1-P0.4)") (class "Default")
      (node (ref "R6") (pin "1") (pinfunction "1_1") (pintype "passive"))
      (node (ref "U1") (pin "33") (pinfunction "P0.4_33") (pintype "passive"))
    )
    (net (code "65") (name "Net-(U1-P0.5)") (class "Default")
      (node (ref "R7") (pin "1") (pinfunction "1_1") (pintype "passive"))
      (node (ref "U1") (pin "32") (pinfunction "P0.5_32") (pintype "passive"))
    )
    (net (code "66") (name "Net-(U1-P0.6)") (class "Default")
      (node (ref "R8") (pin "1") (pinfunction "1_1") (pintype "passive"))
      (node (ref "U1") (pin "31") (pinfunction "P0.6_31") (pintype "passive"))
    )
    (net (code "67") (name "Net-(U1-P0.7)") (class "Default")
      (node (ref "R9") (pin "1") (pinfunction "1_1") (pintype "passive"))
      (node (ref "U1") (pin "30") (pinfunction "P0.7_30") (pintype "passive"))
    )
    (net (code "68") (name "Net-(U1-P1.0{slash}T2)") (class "Default")
      (node (ref "L1") (pin "3") (pinfunction "3_3") (pintype "passive"))
      (node (ref "U1") (pin "40") (pinfunction "P1.0/T2_40") (pintype "passive"))
    )
    (net (code "69") (name "Net-(U1-P1.1{slash}T2EX)") (class "Default")
      (node (ref "L1") (pin "1") (pinfunction "1_1") (pintype "passive"))
      (node (ref "U1") (pin "41") (pinfunction "P1.1/T2EX_41") (pintype "passive"))
    )
    (net (code "70") (name "Net-(U1-P3.0(RXD))") (class "Default")
      (node (ref "P1") (pin "4") (pinfunction "4_4") (pintype "passive"))
      (node (ref "U1") (pin "5") (pinfunction "P3.0(RXD)_5") (pintype "passive"))
    )
    (net (code "71") (name "Net-(U1-P3.1(TXD))") (class "Default")
      (node (ref "P1") (pin "5") (pinfunction "5_5") (pintype "passive"))
      (node (ref "U1") (pin "7") (pinfunction "P3.1(TXD)_7") (pintype "passive"))
    )
    (net (code "72") (name "Net-(U1-RST)") (class "Default")
      (node (ref "C8") (pin "2") (pinfunction "2_2") (pintype "passive"))
      (node (ref "R18") (pin "2") (pinfunction "2_2") (pintype "passive"))
      (node (ref "S1") (pin "1") (pinfunction "1_1") (pintype "passive"))
      (node (ref "U1") (pin "4") (pinfunction "RST_4") (pintype "passive"))
    )
    (net (code "73") (name "Net-(U1-XTAL1)") (class "Default")
      (node (ref "C7") (pin "2") (pinfunction "2_2") (pintype "passive"))
      (node (ref "U1") (pin "15") (pinfunction "XTAL1_15") (pintype "passive"))
      (node (ref "Y1") (pin "2") (pinfunction "2_2") (pintype "passive"))
    )
    (net (code "74") (name "Net-(U1-XTAL2)") (class "Default")
      (node (ref "C6") (pin "2") (pinfunction "2_2") (pintype "passive"))
      (node (ref "U1") (pin "14") (pinfunction "XTAL2_14") (pintype "passive"))
      (node (ref "Y1") (pin "1") (pinfunction "1_1") (pintype "passive"))
    )
    (net (code "75") (name "Net-(VR1-Vout)") (class "Default")
      (node (ref "C2") (pin "1") (pinfunction "1_1") (pintype "passive"))
      (node (ref "C3") (pin "1") (pinfunction "1_1") (pintype "passive"))
      (node (ref "C5") (pin "1") (pinfunction "1_1") (pintype "passive"))
      (node (ref "P1") (pin "7") (pinfunction "7_7") (pintype "passive"))
      (node (ref "VR1") (pin "3") (pinfunction "Vout_3") (pintype "passive"))
      (node (ref "VR2") (pin "3") (pinfunction "Vin_3") (pintype "passive"))
    )
    (net (code "76") (name "VCC") (class "Default")
      (node (ref "C1") (pin "1") (pinfunction "1_1") (pintype "passive"))
      (node (ref "D1") (pin "1") (pinfunction "K_1") (pintype "passive"))
      (node (ref "D10") (pin "1") (pinfunction "A_1") (pintype "passive"))
      (node (ref "D11") (pin "1") (pinfunction "A_1") (pintype "passive"))
      (node (ref "D12") (pin "1") (pinfunction "A_1") (pintype "passive"))
      (node (ref "D13") (pin "1") (pinfunction "A_1") (pintype "passive"))
      (node (ref "D14") (pin "1") (pinfunction "A_1") (pintype "passive"))
      (node (ref "D15") (pin "1") (pinfunction "A_1") (pintype "passive"))
      (node (ref "D16") (pin "1") (pinfunction "A_1") (pintype "passive"))
      (node (ref "D2") (pin "1") (pinfunction "K_1") (pintype "passive"))
      (node (ref "D3") (pin "1") (pinfunction "K_1") (pintype "passive"))
      (node (ref "D4") (pin "1") (pinfunction "K_1") (pintype "passive"))
      (node (ref "D5") (pin "1") (pinfunction "K_1") (pintype "passive"))
      (node (ref "D6") (pin "1") (pinfunction "K_1") (pintype "passive"))
      (node (ref "D7") (pin "1") (pinfunction "K_1") (pintype "passive"))
      (node (ref "D8") (pin "1") (pinfunction "K_1") (pintype "passive"))
      (node (ref "D9") (pin "1") (pinfunction "A_1") (pintype "passive"))
      (node (ref "K1") (pin "4") (pinfunction "T1_4") (pintype "passive"))
      (node (ref "K2") (pin "4") (pinfunction "T1_4") (pintype "passive"))
      (node (ref "K3") (pin "4") (pinfunction "T1_4") (pintype "passive"))
      (node (ref "K4") (pin "4") (pinfunction "T1_4") (pintype "passive"))
      (node (ref "K5") (pin "4") (pinfunction "T1_4") (pintype "passive"))
      (node (ref "K6") (pin "4") (pinfunction "T1_4") (pintype "passive"))
      (node (ref "K7") (pin "4") (pinfunction "T1_4") (pintype "passive"))
      (node (ref "K8") (pin "4") (pinfunction "T1_4") (pintype "passive"))
      (node (ref "P2") (pin "1") (pinfunction "1_1") (pintype "passive"))
      (node (ref "VR1") (pin "1") (pinfunction "Vin_1") (pintype "passive"))
    )
    (net (code "77") (name "unconnected-(K1-NC-Pad2)") (class "Default")
      (node (ref "K1") (pin "2") (pinfunction "NC_2") (pintype "passive"))
    )
    (net (code "78") (name "unconnected-(K2-NC-Pad2)") (class "Default")
      (node (ref "K2") (pin "2") (pinfunction "NC_2") (pintype "passive"))
    )
    (net (code "79") (name "unconnected-(K3-NC-Pad2)") (class "Default")
      (node (ref "K3") (pin "2") (pinfunction "NC_2") (pintype "passive"))
    )
    (net (code "80") (name "unconnected-(K4-NC-Pad2)") (class "Default")
      (node (ref "K4") (pin "2") (pinfunction "NC_2") (pintype "passive"))
    )
    (net (code "81") (name "unconnected-(K5-NC-Pad2)") (class "Default")
      (node (ref "K5") (pin "2") (pinfunction "NC_2") (pintype "passive"))
    )
    (net (code "82") (name "unconnected-(K6-NC-Pad2)") (class "Default")
      (node (ref "K6") (pin "2") (pinfunction "NC_2") (pintype "passive"))
    )
    (net (code "83") (name "unconnected-(K7-NC-Pad2)") (class "Default")
      (node (ref "K7") (pin "2") (pinfunction "NC_2") (pintype "passive"))
    )
    (net (code "84") (name "unconnected-(K8-NC-Pad2)") (class "Default")
      (node (ref "K8") (pin "2") (pinfunction "NC_2") (pintype "passive"))
    )
    (net (code "85") (name "unconnected-(P1-Pad1)") (class "Default")
      (node (ref "P1") (pin "1") (pinfunction "1_1") (pintype "passive"))
    )
    (net (code "86") (name "unconnected-(P1-Pad2)") (class "Default")
      (node (ref "P1") (pin "2") (pinfunction "2_2") (pintype "passive"))
    )
    (net (code "87") (name "unconnected-(P1-Pad3)") (class "Default")
      (node (ref "P1") (pin "3") (pinfunction "3_3") (pintype "passive"))
    )
    (net (code "88") (name "unconnected-(U1-ALE-Pad27)") (class "Default")
      (node (ref "U1") (pin "27") (pinfunction "ALE_27") (pintype "passive"))
    )
    (net (code "89") (name "unconnected-(U1-P1.2-Pad42)") (class "Default")
      (node (ref "U1") (pin "42") (pinfunction "P1.2_42") (pintype "passive"))
    )
    (net (code "90") (name "unconnected-(U1-P1.3-Pad43)") (class "Default")
      (node (ref "U1") (pin "43") (pinfunction "P1.3_43") (pintype "passive"))
    )
    (net (code "91") (name "unconnected-(U1-P1.4-Pad44)") (class "Default")
      (node (ref "U1") (pin "44") (pinfunction "P1.4_44") (pintype "passive"))
    )
    (net (code "92") (name "unconnected-(U1-P1.5-Pad1)") (class "Default")
      (node (ref "U1") (pin "1") (pinfunction "P1.5_1") (pintype "passive"))
    )
    (net (code "93") (name "unconnected-(U1-P1.6-Pad2)") (class "Default")
      (node (ref "U1") (pin "2") (pinfunction "P1.6_2") (pintype "passive"))
    )
    (net (code "94") (name "unconnected-(U1-P1.7-Pad3)") (class "Default")
      (node (ref "U1") (pin "3") (pinfunction "P1.7_3") (pintype "passive"))
    )
    (net (code "95") (name "unconnected-(U1-P2.0-Pad18)") (class "Default")
      (node (ref "U1") (pin "18") (pinfunction "P2.0_18") (pintype "passive"))
    )
    (net (code "96") (name "unconnected-(U1-P2.1-Pad19)") (class "Default")
      (node (ref "U1") (pin "19") (pinfunction "P2.1_19") (pintype "passive"))
    )
    (net (code "97") (name "unconnected-(U1-P2.2-Pad20)") (class "Default")
      (node (ref "U1") (pin "20") (pinfunction "P2.2_20") (pintype "passive"))
    )
    (net (code "98") (name "unconnected-(U1-P2.3-Pad21)") (class "Default")
      (node (ref "U1") (pin "21") (pinfunction "P2.3_21") (pintype "passive"))
    )
    (net (code "99") (name "unconnected-(U1-P2.4-Pad22)") (class "Default")
      (node (ref "U1") (pin "22") (pinfunction "P2.4_22") (pintype "passive"))
    )
    (net (code "100") (name "unconnected-(U1-P2.5-Pad23)") (class "Default")
      (node (ref "U1") (pin "23") (pinfunction "P2.5_23") (pintype "passive"))
    )
    (net (code "101") (name "unconnected-(U1-P2.6-Pad24)") (class "Default")
      (node (ref "U1") (pin "24") (pinfunction "P2.6_24") (pintype "passive"))
    )
    (net (code "102") (name "unconnected-(U1-P2.7-Pad25)") (class "Default")
      (node (ref "U1") (pin "25") (pinfunction "P2.7_25") (pintype "passive"))
    )
    (net (code "103") (name "unconnected-(U1-P3.2(~{INT0})-Pad8)") (class "Default")
      (node (ref "U1") (pin "8") (pinfunction "P3.2(~{INT0})_8") (pintype "passive"))
    )
    (net (code "104") (name "unconnected-(U1-P3.3(~{INT1})-Pad9)") (class "Default")
      (node (ref "U1") (pin "9") (pinfunction "P3.3(~{INT1})_9") (pintype "passive"))
    )
    (net (code "105") (name "unconnected-(U1-P3.4(T0)-Pad10)") (class "Default")
      (node (ref "U1") (pin "10") (pinfunction "P3.4(T0)_10") (pintype "passive"))
    )
    (net (code "106") (name "unconnected-(U1-P3.5(T1)-Pad11)") (class "Default")
      (node (ref "U1") (pin "11") (pinfunction "P3.5(T1)_11") (pintype "passive"))
    )
    (net (code "107") (name "unconnected-(U1-P3.6(~{WR})-Pad12)") (class "Default")
      (node (ref "U1") (pin "12") (pinfunction "P3.6(~{WR})_12") (pintype "passive"))
    )
    (net (code "108") (name "unconnected-(U1-P3.7(~{RD})-Pad13)") (class "Default")
      (node (ref "U1") (pin "13") (pinfunction "P3.7(~{RD})_13") (pintype "passive"))
    )
    (net (code "109") (name "unconnected-(U1-P4.0-Pad17)") (class "Default")
      (node (ref "U1") (pin "17") (pinfunction "P4.0_17") (pintype "passive"))
    )
    (net (code "110") (name "unconnected-(U1-P4.1-Pad28)") (class "Default")
      (node (ref "U1") (pin "28") (pinfunction "P4.1_28") (pintype "passive"))
    )
    (net (code "111") (name "unconnected-(U1-P4.2{slash}~{INT3}-Pad39)") (class "Default")
      (node (ref "U1") (pin "39") (pinfunction "P4.2/~{INT3}_39") (pintype "passive"))
    )
    (net (code "112") (name "unconnected-(U1-P4.3{slash}~{INT2}-Pad6)") (class "Default")
      (node (ref "U1") (pin "6") (pinfunction "P4.3/~{INT2}_6") (pintype "passive"))
    )
    (net (code "113") (name "unconnected-(U1-~{PSEN}-Pad26)") (class "Default")
      (node (ref "U1") (pin "26") (pinfunction "~{PSEN}_26") (pintype "passive"))
    )
  )
)
